# main-board.net
KiCad netlist of a schematic drawn in EAGLE
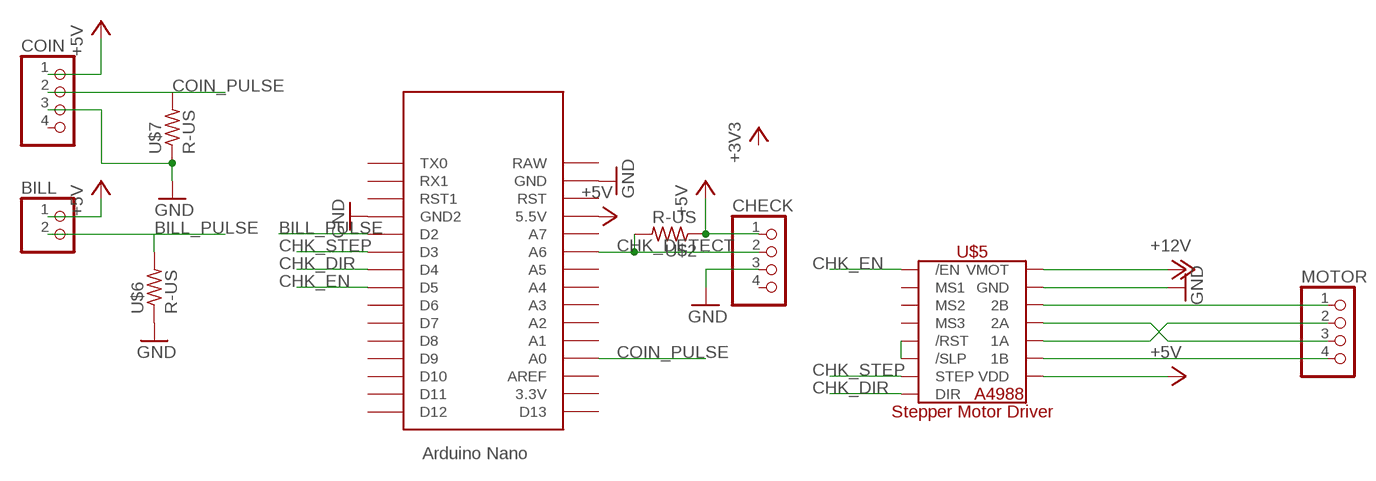
[diagram p0: schematic, sheet 1]

(export (version "E")
  (design (tool "Eeschema 10.0.6"))
  (components
    (comp (ref "BILL")
      (value "PINHD-1X2")
      (footprint "eagle-import:1X02")
      (libsource (lib "eagle-import") (part "PINHD-1X2"))
    )
    (comp (ref "CHECK")
      (value "PINHD-1X4")
      (footprint "eagle-import:1X04")
      (libsource (lib "eagle-import") (part "PINHD-1X4"))
    )
    (comp (ref "COIN")
      (value "PINHD-1X4")
      (footprint "eagle-import:1X04")
      (libsource (lib "eagle-import") (part "PINHD-1X4"))
    )
    (comp (ref "MOTOR")
      (value "PINHD-1X4")
      (footprint "eagle-import:1X04")
      (libsource (lib "eagle-import") (part "PINHD-1X4"))
    )
    (comp (ref "U$1")
      (value "NANO")
      (footprint "eagle-import:NANO")
      (libsource (lib "eagle-import") (part "NANO"))
    )
    (comp (ref "U$2")
      (value "R-US")
      (footprint "eagle-import:0204_7")
      (libsource (lib "eagle-import") (part "R-US"))
    )
    (comp (ref "U$5")
      (value "A4988_STEP")
      (footprint "eagle-import:A4988_STEP")
      (libsource (lib "eagle-import") (part "A4988_STEP"))
    )
    (comp (ref "U$6")
      (value "R-US")
      (footprint "eagle-import:0204_7")
      (libsource (lib "eagle-import") (part "R-US"))
    )
    (comp (ref "U$7")
      (value "R-US")
      (footprint "eagle-import:0204_7")
      (libsource (lib "eagle-import") (part "R-US"))
    )
  )
  (nets
    (net (code "2") (name "+5V") (class "Default")
      (node (ref "BILL") (pin "1") (pinfunction "1_1") (pintype "passive"))
      (node (ref "CHECK") (pin "1") (pinfunction "1_1") (pintype "passive"))
      (node (ref "COIN") (pin "1") (pinfunction "1_1") (pintype "passive"))
      (node (ref "U$1") (pin "5V") (pinfunction "5.5V_5V") (pintype "bidirectional"))
      (node (ref "U$2") (pin "1") (pinfunction "1_1") (pintype "passive"))
      (node (ref "U$5") (pin "VDD") (pinfunction "VDD_VDD") (pintype "bidirectional"))
    )
    (net (code "3") (name "+12V") (class "Default")
      (node (ref "U$5") (pin "VMOT") (pinfunction "VMOT_VMOT") (pintype "bidirectional"))
    )
    (net (code "4") (name "/BILL_PULSE") (class "Default")
      (node (ref "BILL") (pin "2") (pinfunction "2_2") (pintype "passive"))
      (node (ref "U$1") (pin "D2") (pinfunction "D2_D2") (pintype "bidirectional"))
      (node (ref "U$6") (pin "2") (pinfunction "2_2") (pintype "passive"))
    )
    (net (code "5") (name "/CHK_DETECT") (class "Default")
      (node (ref "CHECK") (pin "2") (pinfunction "2_2") (pintype "passive"))
      (node (ref "U$1") (pin "A6") (pinfunction "A6_A6") (pintype "bidirectional"))
      (node (ref "U$2") (pin "2") (pinfunction "2_2") (pintype "passive"))
    )
    (net (code "6") (name "/CHK_DIR") (class "Default")
      (node (ref "U$1") (pin "D4") (pinfunction "D4_D4") (pintype "bidirectional"))
      (node (ref "U$5") (pin "DIR") (pinfunction "DIR_DIR") (pintype "bidirectional"))
    )
    (net (code "7") (name "/CHK_EN") (class "Default")
      (node (ref "U$1") (pin "D5") (pinfunction "D5_D5") (pintype "bidirectional"))
      (node (ref "U$5") (pin "/EN") (pinfunction "/EN_/EN") (pintype "bidirectional"))
    )
    (net (code "8") (name "/CHK_STEP") (class "Default")
      (node (ref "U$1") (pin "D3") (pinfunction "D3_D3") (pintype "bidirectional"))
      (node (ref "U$5") (pin "STEP") (pinfunction "STEP_STEP") (pintype "bidirectional"))
    )
    (net (code "9") (name "/COIN_PULSE") (class "Default")
      (node (ref "COIN") (pin "2") (pinfunction "2_2") (pintype "passive"))
      (node (ref "U$1") (pin "A0") (pinfunction "A0_A0") (pintype "bidirectional"))
      (node (ref "U$7") (pin "2") (pinfunction "2_2") (pintype "passive"))
    )
    (net (code "10") (name "GND") (class "Default")
      (node (ref "CHECK") (pin "3") (pinfunction "3_3") (pintype "passive"))
      (node (ref "COIN") (pin "3") (pinfunction "3_3") (pintype "passive"))
      (node (ref "U$1") (pin "GND") (pinfunction "GND_GND") (pintype "bidirectional"))
      (node (ref "U$1") (pin "GND1") (pinfunction "GND2_GND1") (pintype "bidirectional"))
      (node (ref "U$5") (pin "GND") (pinfunction "GND_GND") (pintype "bidirectional"))
      (node (ref "U$5") (pin "GND2") (pinfunction "GND_GND2") (pintype "bidirectional"))
      (node (ref "U$6") (pin "1") (pinfunction "1_1") (pintype "passive"))
      (node (ref "U$7") (pin "1") (pinfunction "1_1") (pintype "passive"))
    )
    (net (code "11") (name "Net-(MOTOR-Pad1)") (class "Default")
      (node (ref "MOTOR") (pin "1") (pinfunction "1_1") (pintype "passive"))
      (node (ref "U$5") (pin "2B") (pinfunction "2B_2B") (pintype "bidirectional"))
    )
    (net (code "12") (name "Net-(MOTOR-Pad2)") (class "Default")
      (node (ref "MOTOR") (pin "2") (pinfunction "2_2") (pintype "passive"))
      (node (ref "U$5") (pin "1A") (pinfunction "1A_1A") (pintype "bidirectional"))
    )
    (net (code "13") (name "Net-(MOTOR-Pad3)") (class "Default")
      (node (ref "MOTOR") (pin "3") (pinfunction "3_3") (pintype "passive"))
      (node (ref "U$5") (pin "2A") (pinfunction "2A_2A") (pintype "bidirectional"))
    )
    (net (code "14") (name "Net-(MOTOR-Pad4)") (class "Default")
      (node (ref "MOTOR") (pin "4") (pinfunction "4_4") (pintype "passive"))
      (node (ref "U$5") (pin "1B") (pinfunction "1B_1B") (pintype "bidirectional"))
    )
    (net (code "15") (name "Net-(U$5-Pad{slash}RST)") (class "Default")
      (node (ref "U$5") (pin "/RST") (pinfunction "/RST_/RST") (pintype "bidirectional"))
      (node (ref "U$5") (pin "/SLP") (pinfunction "/SLP_/SLP") (pintype "bidirectional"))
    )
    (net (code "16") (name "unconnected-(CHECK-Pad4)") (class "Default")
      (node (ref "CHECK") (pin "4") (pinfunction "4_4") (pintype "passive"))
    )
    (net (code "17") (name "unconnected-(COIN-Pad4)") (class "Default")
      (node (ref "COIN") (pin "4") (pinfunction "4_4") (pintype "passive"))
    )
    (net (code "18") (name "unconnected-(U$1-Pad3.3V)") (class "Default")
      (node (ref "U$1") (pin "3.3V") (pinfunction "3.3V_3.3V") (pintype "bidirectional"))
    )
    (net (code "19") (name "unconnected-(U$1-PadA1)") (class "Default")
      (node (ref "U$1") (pin "A1") (pinfunction "A1_A1") (pintype "bidirectional"))
    )
    (net (code "20") (name "unconnected-(U$1-PadA2)") (class "Default")
      (node (ref "U$1") (pin "A2") (pinfunction "A2_A2") (pintype "bidirectional"))
    )
    (net (code "21") (name "unconnected-(U$1-PadA3)") (class "Default")
      (node (ref "U$1") (pin "A3") (pinfunction "A3_A3") (pintype "bidirectional"))
    )
    (net (code "22") (name "unconnected-(U$1-PadA4)") (class "Default")
      (node (ref "U$1") (pin "A4") (pinfunction "A4_A4") (pintype "bidirectional"))
    )
    (net (code "23") (name "unconnected-(U$1-PadA5)") (class "Default")
      (node (ref "U$1") (pin "A5") (pinfunction "A5_A5") (pintype "bidirectional"))
    )
    (net (code "24") (name "unconnected-(U$1-PadA7)") (class "Default")
      (node (ref "U$1") (pin "A7") (pinfunction "A7_A7") (pintype "bidirectional"))
    )
    (net (code "25") (name "unconnected-(U$1-PadAREF)") (class "Default")
      (node (ref "U$1") (pin "AREF") (pinfunction "AREF_AREF") (pintype "bidirectional"))
    )
    (net (code "26") (name "unconnected-(U$1-PadD6)") (class "Default")
      (node (ref "U$1") (pin "D6") (pinfunction "D6_D6") (pintype "bidirectional"))
    )
    (net (code "27") (name "unconnected-(U$1-PadD7)") (class "Default")
      (node (ref "U$1") (pin "D7") (pinfunction "D7_D7") (pintype "bidirectional"))
    )
    (net (code "28") (name "unconnected-(U$1-PadD8)") (class "Default")
      (node (ref "U$1") (pin "D8") (pinfunction "D8_D8") (pintype "bidirectional"))
    )
    (net (code "29") (name "unconnected-(U$1-PadD9)") (class "Default")
      (node (ref "U$1") (pin "D9") (pinfunction "D9_D9") (pintype "bidirectional"))
    )
    (net (code "30") (name "unconnected-(U$1-PadD10)") (class "Default")
      (node (ref "U$1") (pin "D10") (pinfunction "D10_D10") (pintype "bidirectional"))
    )
    (net (code "31") (name "unconnected-(U$1-PadD11)") (class "Default")
      (node (ref "U$1") (pin "D11") (pinfunction "D11_D11") (pintype "bidirectional"))
    )
    (net (code "32") (name "unconnected-(U$1-PadD12)") (class "Default")
      (node (ref "U$1") (pin "D12") (pinfunction "D12_D12") (pintype "bidirectional"))
    )
    (net (code "33") (name "unconnected-(U$1-PadD13)") (class "Default")
      (node (ref "U$1") (pin "D13") (pinfunction "D13_D13") (pintype "bidirectional"))
    )
    (net (code "34") (name "unconnected-(U$1-PadICSP1)") (class "Default")
      (node (ref "U$1") (pin "ICSP1") (pinfunction "ICSP1_ICSP1") (pintype "bidirectional"))
    )
    (net (code "35") (name "unconnected-(U$1-PadICSP2)") (class "Default")
      (node (ref "U$1") (pin "ICSP2") (pinfunction "ICSP2_ICSP2") (pintype "bidirectional"))
    )
    (net (code "36") (name "unconnected-(U$1-PadICSP3)") (class "Default")
      (node (ref "U$1") (pin "ICSP3") (pinfunction "ICSP3_ICSP3") (pintype "bidirectional"))
    )
    (net (code "37") (name "unconnected-(U$1-PadICSP4)") (class "Default")
      (node (ref "U$1") (pin "ICSP4") (pinfunction "ICSP4_ICSP4") (pintype "bidirectional"))
    )
    (net (code "38") (name "unconnected-(U$1-PadICSP5)") (class "Default")
      (node (ref "U$1") (pin "ICSP5") (pinfunction "ICSP5_ICSP5") (pintype "bidirectional"))
    )
    (net (code "39") (name "unconnected-(U$1-PadICSP6)") (class "Default")
      (node (ref "U$1") (pin "ICSP6") (pinfunction "ICSP6_ICSP6") (pintype "bidirectional"))
    )
    (net (code "40") (name "unconnected-(U$1-PadRAW)") (class "Default")
      (node (ref "U$1") (pin "RAW") (pinfunction "RAW_RAW") (pintype "bidirectional"))
    )
    (net (code "41") (name "unconnected-(U$1-PadRST)") (class "Default")
      (node (ref "U$1") (pin "RST") (pinfunction "RST_RST") (pintype "bidirectional"))
    )
    (net (code "42") (name "unconnected-(U$1-PadRST1)") (class "Default")
      (node (ref "U$1") (pin "RST1") (pinfunction "RST1_RST1") (pintype "bidirectional"))
    )
    (net (code "43") (name "unconnected-(U$1-PadRX1)") (class "Default")
      (node (ref "U$1") (pin "RX1") (pinfunction "RX1_RX1") (pintype "bidirectional"))
    )
    (net (code "44") (name "unconnected-(U$1-PadTX0)") (class "Default")
      (node (ref "U$1") (pin "TX0") (pinfunction "TX0_TX0") (pintype "bidirectional"))
    )
    (net (code "45") (name "unconnected-(U$5-PadMS1)") (class "Default")
      (node (ref "U$5") (pin "MS1") (pinfunction "MS1_MS1") (pintype "bidirectional"))
    )
    (net (code "46") (name "unconnected-(U$5-PadMS2)") (class "Default")
      (node (ref "U$5") (pin "MS2") (pinfunction "MS2_MS2") (pintype "bidirectional"))
    )
    (net (code "47") (name "unconnected-(U$5-PadMS3)") (class "Default")
      (node (ref "U$5") (pin "MS3") (pinfunction "MS3_MS3") (pintype "bidirectional"))
    )
  )
)
